# FM-Superregenerative-Receiver-1.net
KiCad netlist of a schematic drawn in EAGLE
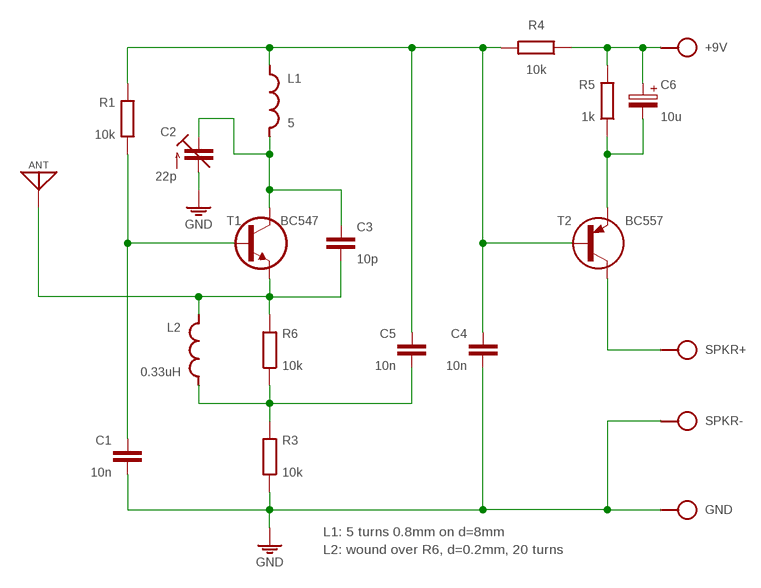
[diagram p0: schematic, sheet 1]

(export (version "E")
  (design (tool "Eeschema 10.0.6"))
  (components
    (comp (ref "+9V")
      (value "SPAD")
      (footprint "eagle-import:SPAD")
      (libsource (lib "eagle-import") (part "SPAD"))
    )
    (comp (ref "ANT")
      (value "ANT")
      (footprint "eagle-import:SPAD")
      (libsource (lib "eagle-import") (part "ANT"))
    )
    (comp (ref "C1")
      (value "10n")
      (footprint "eagle-import:C050-020X036")
      (libsource (lib "eagle-import") (part "C050-020X036"))
    )
    (comp (ref "C2")
      (value "22p")
      (footprint "eagle-import:TRIM-2222-808")
      (libsource (lib "eagle-import") (part "C-TR-PH201272222-808-2PINB"))
    )
    (comp (ref "C3")
      (value "10p")
      (footprint "eagle-import:C050-020X036")
      (libsource (lib "eagle-import") (part "C050-020X036"))
    )
    (comp (ref "C4")
      (value "10n")
      (footprint "eagle-import:C050-020X036_V")
      (libsource (lib "eagle-import") (part "C050-020X036/V"))
    )
    (comp (ref "C5")
      (value "10n")
      (footprint "eagle-import:C050-020X036_V")
      (libsource (lib "eagle-import") (part "C050-020X036/V"))
    )
    (comp (ref "C6")
      (value "10u")
      (footprint "eagle-import:E2,5-3")
      (libsource (lib "eagle-import") (part "CPOLE2,5-3"))
    )
    (comp (ref "GND")
      (value "SPAD")
      (footprint "eagle-import:SPAD")
      (libsource (lib "eagle-import") (part "SPAD"))
    )
    (comp (ref "L1")
      (value "5")
      (footprint "eagle-import:L-04_7V-X")
      (libsource (lib "eagle-import") (part "L-SHORTL-04/7V-X"))
    )
    (comp (ref "L2")
      (value "0.33uH")
      (footprint "eagle-import:L-04_7V-X")
      (libsource (lib "eagle-import") (part "L-SHORTL-04/7V-X"))
    )
    (comp (ref "R1")
      (value "10k")
      (footprint "eagle-import:0202_7")
      (libsource (lib "eagle-import") (part "R0202/7"))
    )
    (comp (ref "R3")
      (value "10k")
      (footprint "eagle-import:0202V")
      (libsource (lib "eagle-import") (part "R0202V"))
    )
    (comp (ref "R4")
      (value "10k")
      (footprint "eagle-import:0202_7")
      (libsource (lib "eagle-import") (part "R0202/7"))
    )
    (comp (ref "R5")
      (value "1k")
      (footprint "eagle-import:0202_7-V")
      (libsource (lib "eagle-import") (part "R0202/7-V"))
    )
    (comp (ref "R6")
      (value "10k")
      (footprint "eagle-import:0202_7-V")
      (libsource (lib "eagle-import") (part "R0202/7-V"))
    )
    (comp (ref "SPKR+")
      (value "SPAD")
      (footprint "eagle-import:SPAD")
      (libsource (lib "eagle-import") (part "SPAD"))
    )
    (comp (ref "SPKR-")
      (value "SPAD")
      (footprint "eagle-import:SPAD")
      (libsource (lib "eagle-import") (part "SPAD"))
    )
    (comp (ref "T1")
      (value "BC547")
      (footprint "eagle-import:TO92-CBE")
      (libsource (lib "eagle-import") (part "BC547CBE"))
    )
    (comp (ref "T2")
      (value "BC557")
      (footprint "eagle-import:TO92-CBE-A")
      (libsource (lib "eagle-import") (part "BC557CBE-A"))
    )
  )
  (nets
    (net (code "1") (name "GND") (class "Default")
      (node (ref "C1") (pin "2") (pinfunction "2_2") (pintype "passive"))
      (node (ref "C2") (pin "2") (pinfunction "A_2") (pintype "passive"))
      (node (ref "C4") (pin "2") (pinfunction "2_2") (pintype "passive"))
      (node (ref "GND") (pin "1") (pinfunction "P$1_1") (pintype "bidirectional"))
      (node (ref "R3") (pin "1") (pinfunction "1_1") (pintype "passive"))
      (node (ref "SPKR-") (pin "1") (pinfunction "P$1_1") (pintype "bidirectional"))
    )
    (net (code "2") (name "Net-(+9V-P$1)") (class "Default")
      (node (ref "+9V") (pin "1") (pinfunction "P$1_1") (pintype "bidirectional"))
      (node (ref "C6") (pin "+") (pinfunction "+_+") (pintype "passive"))
      (node (ref "R4") (pin "1") (pinfunction "1_1") (pintype "passive"))
      (node (ref "R5") (pin "2") (pinfunction "2_2") (pintype "passive"))
    )
    (net (code "3") (name "Net-(ANT-Pad1)") (class "Default")
      (node (ref "ANT") (pin "1") (pinfunction "1_1") (pintype "output"))
      (node (ref "C3") (pin "2") (pinfunction "2_2") (pintype "passive"))
      (node (ref "L2") (pin "2") (pinfunction "2_2") (pintype "passive"))
      (node (ref "R6") (pin "2") (pinfunction "2_2") (pintype "passive"))
      (node (ref "T1") (pin "E") (pinfunction "E_E") (pintype "passive"))
    )
    (net (code "4") (name "Net-(C1-Pad1)") (class "Default")
      (node (ref "C1") (pin "1") (pinfunction "1_1") (pintype "passive"))
      (node (ref "R1") (pin "1") (pinfunction "1_1") (pintype "passive"))
      (node (ref "T1") (pin "B") (pinfunction "B_B") (pintype "passive"))
    )
    (net (code "5") (name "Net-(C2-E)") (class "Default")
      (node (ref "C2") (pin "3") (pinfunction "E_3") (pintype "passive"))
      (node (ref "C3") (pin "1") (pinfunction "1_1") (pintype "passive"))
      (node (ref "L1") (pin "1") (pinfunction "1_1") (pintype "passive"))
      (node (ref "T1") (pin "C") (pinfunction "C_C") (pintype "passive"))
    )
    (net (code "6") (name "Net-(C4-Pad1)") (class "Default")
      (node (ref "C4") (pin "1") (pinfunction "1_1") (pintype "passive"))
      (node (ref "C5") (pin "1") (pinfunction "1_1") (pintype "passive"))
      (node (ref "L1") (pin "2") (pinfunction "2_2") (pintype "passive"))
      (node (ref "R1") (pin "2") (pinfunction "2_2") (pintype "passive"))
      (node (ref "R4") (pin "2") (pinfunction "2_2") (pintype "passive"))
      (node (ref "T2") (pin "B") (pinfunction "B_B") (pintype "passive"))
    )
    (net (code "7") (name "Net-(C5-Pad2)") (class "Default")
      (node (ref "C5") (pin "2") (pinfunction "2_2") (pintype "passive"))
      (node (ref "L2") (pin "1") (pinfunction "1_1") (pintype "passive"))
      (node (ref "R3") (pin "2") (pinfunction "2_2") (pintype "passive"))
      (node (ref "R6") (pin "1") (pinfunction "1_1") (pintype "passive"))
    )
    (net (code "8") (name "Net-(C6-Pad-)") (class "Default")
      (node (ref "C6") (pin "-") (pinfunction "-_-") (pintype "passive"))
      (node (ref "R5") (pin "1") (pinfunction "1_1") (pintype "passive"))
      (node (ref "T2") (pin "E") (pinfunction "E_E") (pintype "passive"))
    )
    (net (code "9") (name "Net-(SPKR+-P$1)") (class "Default")
      (node (ref "SPKR+") (pin "1") (pinfunction "P$1_1") (pintype "bidirectional"))
      (node (ref "T2") (pin "C") (pinfunction "C_C") (pintype "passive"))
    )
  )
)
